# LEDToy.net
KiCad netlist of a schematic drawn in EAGLE
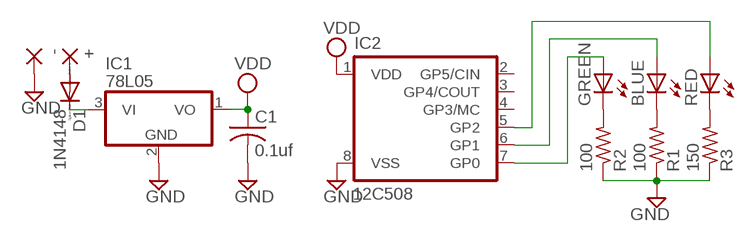
[diagram p0: schematic, sheet 1]

(export (version "E")
  (design (tool "Eeschema 10.0.6"))
  (components
    (comp (ref "+")
      (value "2,15/1,0")
      (footprint "eagle-import:2,15_1,0")
      (libsource (lib "eagle-import") (part "2,15/1,0"))
    )
    (comp (ref "-")
      (value "2,15/1,0")
      (footprint "eagle-import:2,15_1,0")
      (libsource (lib "eagle-import") (part "2,15/1,0"))
    )
    (comp (ref "BLUE")
      (value "LED5MM")
      (footprint "eagle-import:LED5MM")
      (libsource (lib "eagle-import") (part "LED5MM"))
    )
    (comp (ref "C1")
      (value "0.1uf")
      (footprint "eagle-import:C050-025X075")
      (libsource (lib "eagle-import") (part "C-US050-025X075"))
    )
    (comp (ref "D1")
      (value "1N4148")
      (footprint "eagle-import:DO35-10")
      (libsource (lib "eagle-import") (part "1N4148DO35-10"))
    )
    (comp (ref "GREEN")
      (value "LED5MM")
      (footprint "eagle-import:LED5MM")
      (libsource (lib "eagle-import") (part "LED5MM"))
    )
    (comp (ref "IC1")
      (value "78L05")
      (footprint "eagle-import:TO92")
      (libsource (lib "eagle-import") (part "78ZL05"))
    )
    (comp (ref "IC2")
      (value "12C508")
      (footprint "eagle-import:DIL8")
      (fields (field (name "MF") "MICROCHIP") (field (name "MPN") "PIC12C508A-04I/P"))
      (libsource (lib "eagle-import") (part "PIC12C?P508"))
    )
    (comp (ref "R1")
      (value "100")
      (footprint "eagle-import:0207_10")
      (libsource (lib "eagle-import") (part "R-US_0207/10"))
    )
    (comp (ref "R2")
      (value "100")
      (footprint "eagle-import:0207_10")
      (libsource (lib "eagle-import") (part "R-US_0207/10"))
    )
    (comp (ref "R3")
      (value "150")
      (footprint "eagle-import:0207_10")
      (libsource (lib "eagle-import") (part "R-US_0207/10"))
    )
    (comp (ref "RED")
      (value "LED5MM")
      (footprint "eagle-import:LED5MM")
      (libsource (lib "eagle-import") (part "LED5MM"))
    )
  )
  (nets
    (net (code "1") (name "GND") (class "Default")
      (node (ref "-") (pin "1") (pinfunction "P_1") (pintype "passive"))
      (node (ref "C1") (pin "2") (pinfunction "2_2") (pintype "passive"))
      (node (ref "IC1") (pin "2") (pinfunction "GND_2") (pintype "passive"))
      (node (ref "IC2") (pin "8") (pinfunction "VSS_8") (pintype "power_in"))
      (node (ref "R1") (pin "1") (pinfunction "1_1") (pintype "passive"))
      (node (ref "R2") (pin "1") (pinfunction "1_1") (pintype "passive"))
      (node (ref "R3") (pin "1") (pinfunction "1_1") (pintype "passive"))
    )
    (net (code "2") (name "Net-(+-P)") (class "Default")
      (node (ref "+") (pin "1") (pinfunction "P_1") (pintype "passive"))
      (node (ref "D1") (pin "A") (pinfunction "A_A") (pintype "passive"))
    )
    (net (code "3") (name "Net-(BLUE-C)") (class "Default")
      (node (ref "BLUE") (pin "K") (pinfunction "C_K") (pintype "passive"))
      (node (ref "R1") (pin "2") (pinfunction "2_2") (pintype "passive"))
    )
    (net (code "4") (name "Net-(GREEN-C)") (class "Default")
      (node (ref "GREEN") (pin "K") (pinfunction "C_K") (pintype "passive"))
      (node (ref "R2") (pin "2") (pinfunction "2_2") (pintype "passive"))
    )
    (net (code "5") (name "Net-(IC1-VI)") (class "Default")
      (node (ref "D1") (pin "C") (pinfunction "C_C") (pintype "passive"))
      (node (ref "IC1") (pin "3") (pinfunction "VI_3") (pintype "input"))
    )
    (net (code "6") (name "Net-(IC2-GP0)") (class "Default")
      (node (ref "GREEN") (pin "A") (pinfunction "A_A") (pintype "passive"))
      (node (ref "IC2") (pin "7") (pinfunction "GP0_7") (pintype "bidirectional"))
    )
    (net (code "7") (name "Net-(IC2-GP1)") (class "Default")
      (node (ref "BLUE") (pin "A") (pinfunction "A_A") (pintype "passive"))
      (node (ref "IC2") (pin "6") (pinfunction "GP1_6") (pintype "bidirectional"))
    )
    (net (code "8") (name "Net-(IC2-GP2)") (class "Default")
      (node (ref "IC2") (pin "5") (pinfunction "GP2_5") (pintype "bidirectional"))
      (node (ref "RED") (pin "A") (pinfunction "A_A") (pintype "passive"))
    )
    (net (code "9") (name "Net-(RED-C)") (class "Default")
      (node (ref "R3") (pin "2") (pinfunction "2_2") (pintype "passive"))
      (node (ref "RED") (pin "K") (pinfunction "C_K") (pintype "passive"))
    )
    (net (code "10") (name "VDD") (class "Default")
      (node (ref "C1") (pin "1") (pinfunction "1_1") (pintype "passive"))
      (node (ref "IC1") (pin "1") (pinfunction "VO_1") (pintype "passive"))
      (node (ref "IC2") (pin "1") (pinfunction "VDD_1") (pintype "power_in"))
    )
    (net (code "11") (name "unconnected-(IC2-GP3{slash}MC-Pad4)") (class "Default")
      (node (ref "IC2") (pin "4") (pinfunction "GP3/MC_4") (pintype "input"))
    )
    (net (code "12") (name "unconnected-(IC2-GP4{slash}COUT-Pad3)") (class "Default")
      (node (ref "IC2") (pin "3") (pinfunction "GP4/COUT_3") (pintype "bidirectional"))
    )
    (net (code "13") (name "unconnected-(IC2-GP5{slash}CIN-Pad2)") (class "Default")
      (node (ref "IC2") (pin "2") (pinfunction "GP5/CIN_2") (pintype "bidirectional"))
    )
  )
)
